# Display.net
KiCad netlist of a schematic drawn in Altium Designer
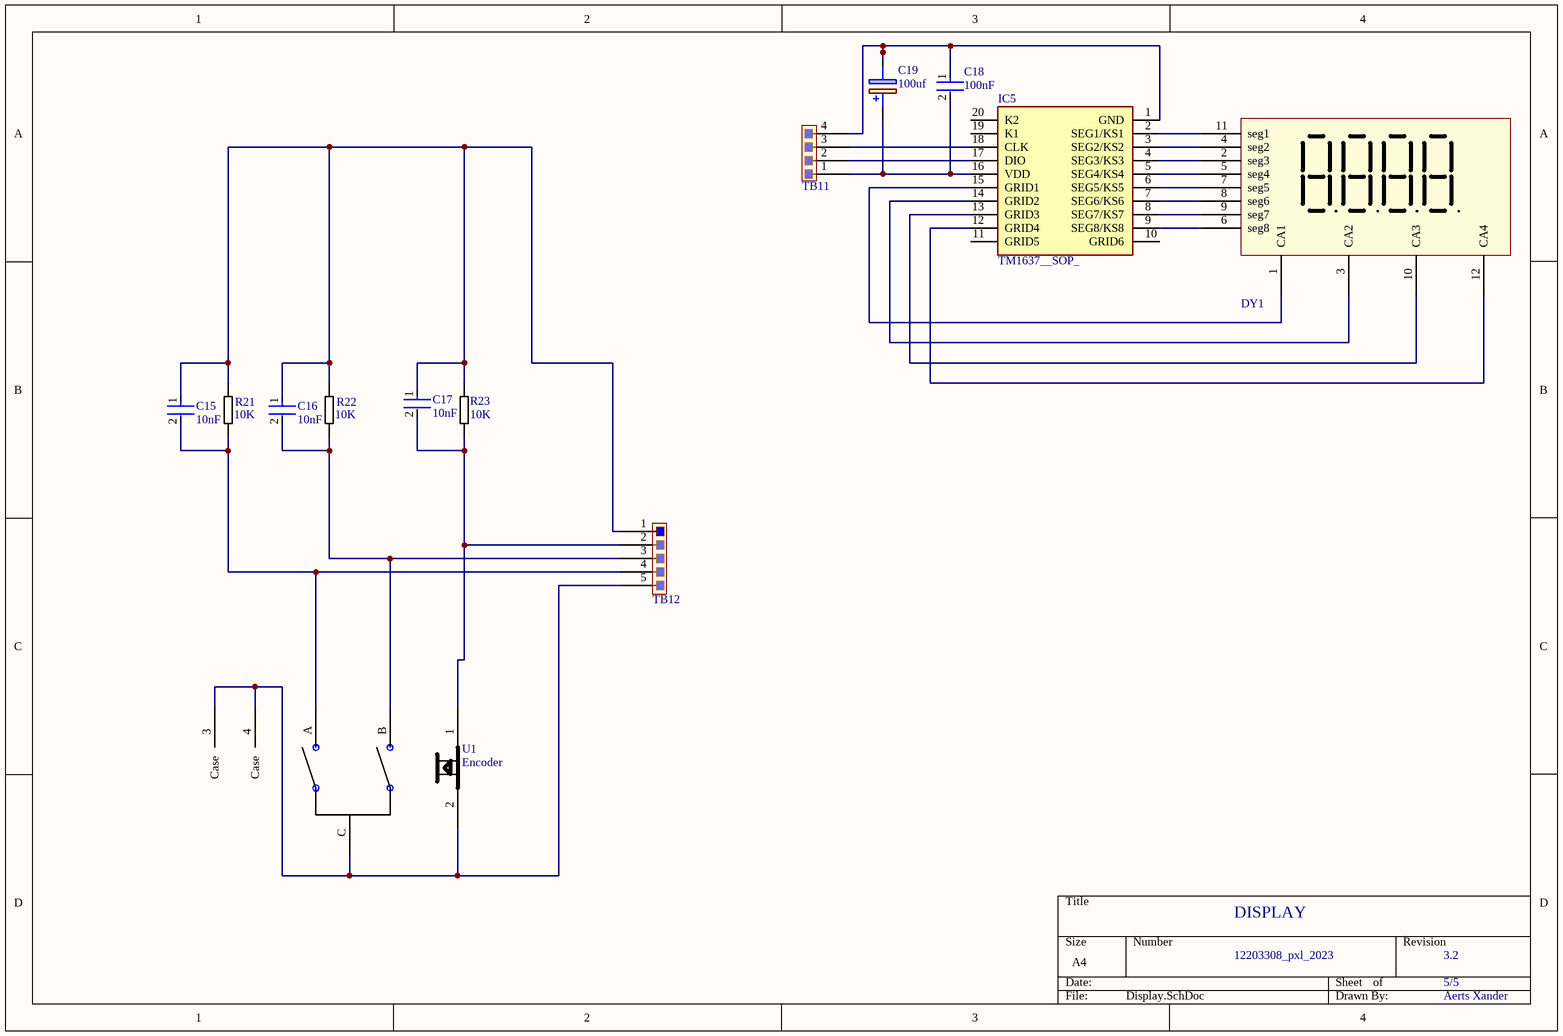
[diagram p0: Display.SchDoc]

(export (version "E")
  (design (tool "Eeschema 10.0.6"))
  (components
    (comp (ref "C15")
      (value "10nF")
      (footprint "0805")
      (description "CAP CER 10000PF 50V X7R 0603")
      (fields (field (name "TOLERANCE") "0.1") (field (name "MANUFACTURER PART NUMBER") "CC0603KRX7R9BB103"))
      (libsource (lib "soldeerstation") (part "Capacitor 0805"))
    )
    (comp (ref "C16")
      (value "10nF")
      (footprint "0805")
      (description "CAP CER 10000PF 50V X7R 0603")
      (fields (field (name "TOLERANCE") "0.1") (field (name "MANUFACTURER PART NUMBER") "CC0603KRX7R9BB103"))
      (libsource (lib "soldeerstation") (part "Capacitor 0805"))
    )
    (comp (ref "C17")
      (value "10nF")
      (footprint "0805")
      (description "CAP CER 10000PF 50V X7R 0603")
      (fields (field (name "TOLERANCE") "0.1") (field (name "MANUFACTURER PART NUMBER") "CC0603KRX7R9BB103"))
      (libsource (lib "soldeerstation") (part "Capacitor 0805"))
    )
    (comp (ref "C18")
      (value "100nF")
      (footprint "0805")
      (description "CAP CER 10000PF 50V X7R 0603")
      (fields (field (name "TOLERANCE") "0.1") (field (name "MANUFACTURER PART NUMBER") "CC0603KRX7R9BB103"))
      (libsource (lib "soldeerstation") (part "Capacitor 0805"))
    )
    (comp (ref "C19")
      (value "100uf")
      (footprint "100uf tht")
      (description "Aluminum Electrolytic Capacitors - Radial Leaded 50V 100uF 20%-MAL213631101E3")
      (fields
        (field (name "MOUSER PART NUMBER") "594-MAL213631101E3")
        (field (name "MANUFACTURER_PART_NUMBER") "MAL213631101E3")
      )
      (libsource (lib "soldeerstation") (part "100uf tht"))
    )
    (comp (ref "DY1")
      (value "4 x sevensegment display")
      (footprint "4 x sevensegment display")
      (libsource (lib "soldeerstation") (part "4 x sevensegment display"))
    )
    (comp (ref "IC5")
      (value "TM1637__SOP_")
      (footprint "sop")
      (description "Integrated Circuit")
      (fields (field (name "MANUFACTURER_PART_NUMBER") "TM1637 (SOP)"))
      (libsource (lib "soldeerstation") (part "TM1637__SOP_"))
    )
    (comp (ref "R21")
      (value "10K")
      (footprint "0805")
      (fields (field (name "MANUFACTURER") "Vishay Dale") (field (name "PART NUMBER") "CRCW08050000Z0EA"))
      (libsource (lib "soldeerstation") (part "resistor"))
    )
    (comp (ref "R22")
      (value "10K")
      (footprint "0805")
      (fields (field (name "MANUFACTURER") "Vishay Dale") (field (name "PART NUMBER") "CRCW08050000Z0EA"))
      (libsource (lib "soldeerstation") (part "resistor"))
    )
    (comp (ref "R23")
      (value "10K")
      (footprint "0805")
      (fields (field (name "MANUFACTURER") "Vishay Dale") (field (name "PART NUMBER") "CRCW08050000Z0EA"))
      (libsource (lib "soldeerstation") (part "resistor"))
    )
    (comp (ref "TB11")
      (value "4x1 header tht")
      (footprint "4x1 header tht")
      (libsource (lib "soldeerstation") (part "4x1 header tht"))
    )
    (comp (ref "TB12")
      (value "5x1 header tht")
      (footprint "5x1 header tht")
      (libsource (lib "soldeerstation") (part "5x1 header tht"))
    )
    (comp (ref "U1")
      (value "Encoder")
      (footprint "Encoder")
      (libsource (lib "soldeerstation") (part "Encoder"))
    )
  )
  (nets
    (net (code "1") (name "Net-(C19-+)") (class "Default")
      (node (ref "C18") (pin "2") (pinfunction "2_2") (pintype "passive"))
      (node (ref "C19") (pin "1") (pinfunction "+_1") (pintype "passive"))
      (node (ref "IC5") (pin "16") (pinfunction "VDD_16") (pintype "passive"))
      (node (ref "TB11") (pin "1") (pinfunction "16_1") (pintype "passive"))
    )
    (net (code "2") (name "Net-(C19--)") (class "Default")
      (node (ref "C18") (pin "1") (pinfunction "1_1") (pintype "passive"))
      (node (ref "C19") (pin "2") (pinfunction "-_2") (pintype "passive"))
      (node (ref "IC5") (pin "1") (pinfunction "GND_1") (pintype "passive"))
      (node (ref "TB11") (pin "4") (pinfunction "19_4") (pintype "passive"))
    )
    (net (code "3") (name "Net-(DY1-CA1)") (class "Default")
      (node (ref "DY1") (pin "1") (pinfunction "CA1_1") (pintype "passive"))
      (node (ref "IC5") (pin "15") (pinfunction "GRID1_15") (pintype "passive"))
    )
    (net (code "4") (name "Net-(DY1-CA2)") (class "Default")
      (node (ref "DY1") (pin "3") (pinfunction "CA2_3") (pintype "passive"))
      (node (ref "IC5") (pin "14") (pinfunction "GRID2_14") (pintype "passive"))
    )
    (net (code "5") (name "Net-(DY1-CA3)") (class "Default")
      (node (ref "DY1") (pin "10") (pinfunction "CA3_10") (pintype "passive"))
      (node (ref "IC5") (pin "13") (pinfunction "GRID3_13") (pintype "passive"))
    )
    (net (code "6") (name "Net-(DY1-CA4)") (class "Default")
      (node (ref "DY1") (pin "12") (pinfunction "CA4_12") (pintype "passive"))
      (node (ref "IC5") (pin "12") (pinfunction "GRID4_12") (pintype "passive"))
    )
    (net (code "7") (name "Net-(DY1-seg1)") (class "Default")
      (node (ref "DY1") (pin "11") (pinfunction "seg1_11") (pintype "passive"))
      (node (ref "IC5") (pin "2") (pinfunction "SEG1/KS1_2") (pintype "passive"))
    )
    (net (code "8") (name "Net-(DY1-seg2)") (class "Default")
      (node (ref "DY1") (pin "4") (pinfunction "seg2_4") (pintype "passive"))
      (node (ref "IC5") (pin "3") (pinfunction "SEG2/KS2_3") (pintype "passive"))
    )
    (net (code "9") (name "Net-(DY1-seg3)") (class "Default")
      (node (ref "DY1") (pin "2") (pinfunction "seg3_2") (pintype "passive"))
      (node (ref "IC5") (pin "4") (pinfunction "SEG3/KS3_4") (pintype "passive"))
    )
    (net (code "10") (name "Net-(DY1-seg4)") (class "Default")
      (node (ref "DY1") (pin "5") (pinfunction "seg4_5") (pintype "passive"))
      (node (ref "IC5") (pin "5") (pinfunction "SEG4/KS4_5") (pintype "passive"))
    )
    (net (code "11") (name "Net-(DY1-seg5)") (class "Default")
      (node (ref "DY1") (pin "7") (pinfunction "seg5_7") (pintype "passive"))
      (node (ref "IC5") (pin "6") (pinfunction "SEG5/KS5_6") (pintype "passive"))
    )
    (net (code "12") (name "Net-(DY1-seg6)") (class "Default")
      (node (ref "DY1") (pin "8") (pinfunction "seg6_8") (pintype "passive"))
      (node (ref "IC5") (pin "7") (pinfunction "SEG6/KS6_7") (pintype "passive"))
    )
    (net (code "13") (name "Net-(DY1-seg7)") (class "Default")
      (node (ref "DY1") (pin "9") (pinfunction "seg7_9") (pintype "passive"))
      (node (ref "IC5") (pin "8") (pinfunction "SEG7/KS7_8") (pintype "passive"))
    )
    (net (code "14") (name "Net-(DY1-seg8)") (class "Default")
      (node (ref "DY1") (pin "6") (pinfunction "seg8_6") (pintype "passive"))
      (node (ref "IC5") (pin "9") (pinfunction "SEG8/KS8_9") (pintype "passive"))
    )
    (net (code "15") (name "Net-(IC5-CLK)") (class "Default")
      (node (ref "IC5") (pin "18") (pinfunction "CLK_18") (pintype "passive"))
      (node (ref "TB11") (pin "3") (pinfunction "18_3") (pintype "passive"))
    )
    (net (code "16") (name "Net-(IC5-DIO)") (class "Default")
      (node (ref "IC5") (pin "17") (pinfunction "DIO_17") (pintype "passive"))
      (node (ref "TB11") (pin "2") (pinfunction "17_2") (pintype "passive"))
    )
    (net (code "17") (name "Net-(TB12-16)") (class "Default")
      (node (ref "C17") (pin "2") (pinfunction "2_2") (pintype "passive"))
      (node (ref "R23") (pin "1") (pinfunction "1_1") (pintype "passive"))
      (node (ref "TB12") (pin "2") (pinfunction "16_2") (pintype "passive"))
      (node (ref "U1") (pin "1") (pinfunction "SW1_1") (pintype "passive"))
    )
    (net (code "18") (name "Net-(TB12-17)") (class "Default")
      (node (ref "C16") (pin "2") (pinfunction "2_2") (pintype "passive"))
      (node (ref "R22") (pin "1") (pinfunction "1_1") (pintype "passive"))
      (node (ref "TB12") (pin "3") (pinfunction "17_3") (pintype "passive"))
      (node (ref "U1") (pin "B") (pinfunction "B_B") (pintype "passive"))
    )
    (net (code "19") (name "Net-(TB12-18)") (class "Default")
      (node (ref "C15") (pin "2") (pinfunction "2_2") (pintype "passive"))
      (node (ref "R21") (pin "1") (pinfunction "1_1") (pintype "passive"))
      (node (ref "TB12") (pin "4") (pinfunction "18_4") (pintype "passive"))
      (node (ref "U1") (pin "A") (pinfunction "A_A") (pintype "passive"))
    )
    (net (code "20") (name "Net-(TB12-19)") (class "Default")
      (node (ref "TB12") (pin "5") (pinfunction "19_5") (pintype "passive"))
      (node (ref "U1") (pin "2") (pinfunction "SW2_2") (pintype "passive"))
      (node (ref "U1") (pin "3") (pinfunction "Case_3") (pintype "passive"))
      (node (ref "U1") (pin "4") (pinfunction "Case_4") (pintype "passive"))
      (node (ref "U1") (pin "C") (pinfunction "3_C") (pintype "passive"))
    )
    (net (code "21") (name "Net-(TB12-20)") (class "Default")
      (node (ref "C15") (pin "1") (pinfunction "1_1") (pintype "passive"))
      (node (ref "C16") (pin "1") (pinfunction "1_1") (pintype "passive"))
      (node (ref "C17") (pin "1") (pinfunction "1_1") (pintype "passive"))
      (node (ref "R21") (pin "2") (pinfunction "2_2") (pintype "passive"))
      (node (ref "R22") (pin "2") (pinfunction "2_2") (pintype "passive"))
      (node (ref "R23") (pin "2") (pinfunction "2_2") (pintype "passive"))
      (node (ref "TB12") (pin "1") (pinfunction "20_1") (pintype "passive"))
    )
    (net (code "22") (name "unconnected-(IC5-GRID5-Pad11)") (class "Default")
      (node (ref "IC5") (pin "11") (pinfunction "GRID5_11") (pintype "passive"))
    )
    (net (code "23") (name "unconnected-(IC5-GRID6-Pad10)") (class "Default")
      (node (ref "IC5") (pin "10") (pinfunction "GRID6_10") (pintype "passive"))
    )
    (net (code "24") (name "unconnected-(IC5-K1-Pad19)") (class "Default")
      (node (ref "IC5") (pin "19") (pinfunction "K1_19") (pintype "passive"))
    )
    (net (code "25") (name "unconnected-(IC5-K2-Pad20)") (class "Default")
      (node (ref "IC5") (pin "20") (pinfunction "K2_20") (pintype "passive"))
    )
  )
)
